# SparkFun_Qwiic_Adapter.net
KiCad netlist of a schematic drawn in EAGLE
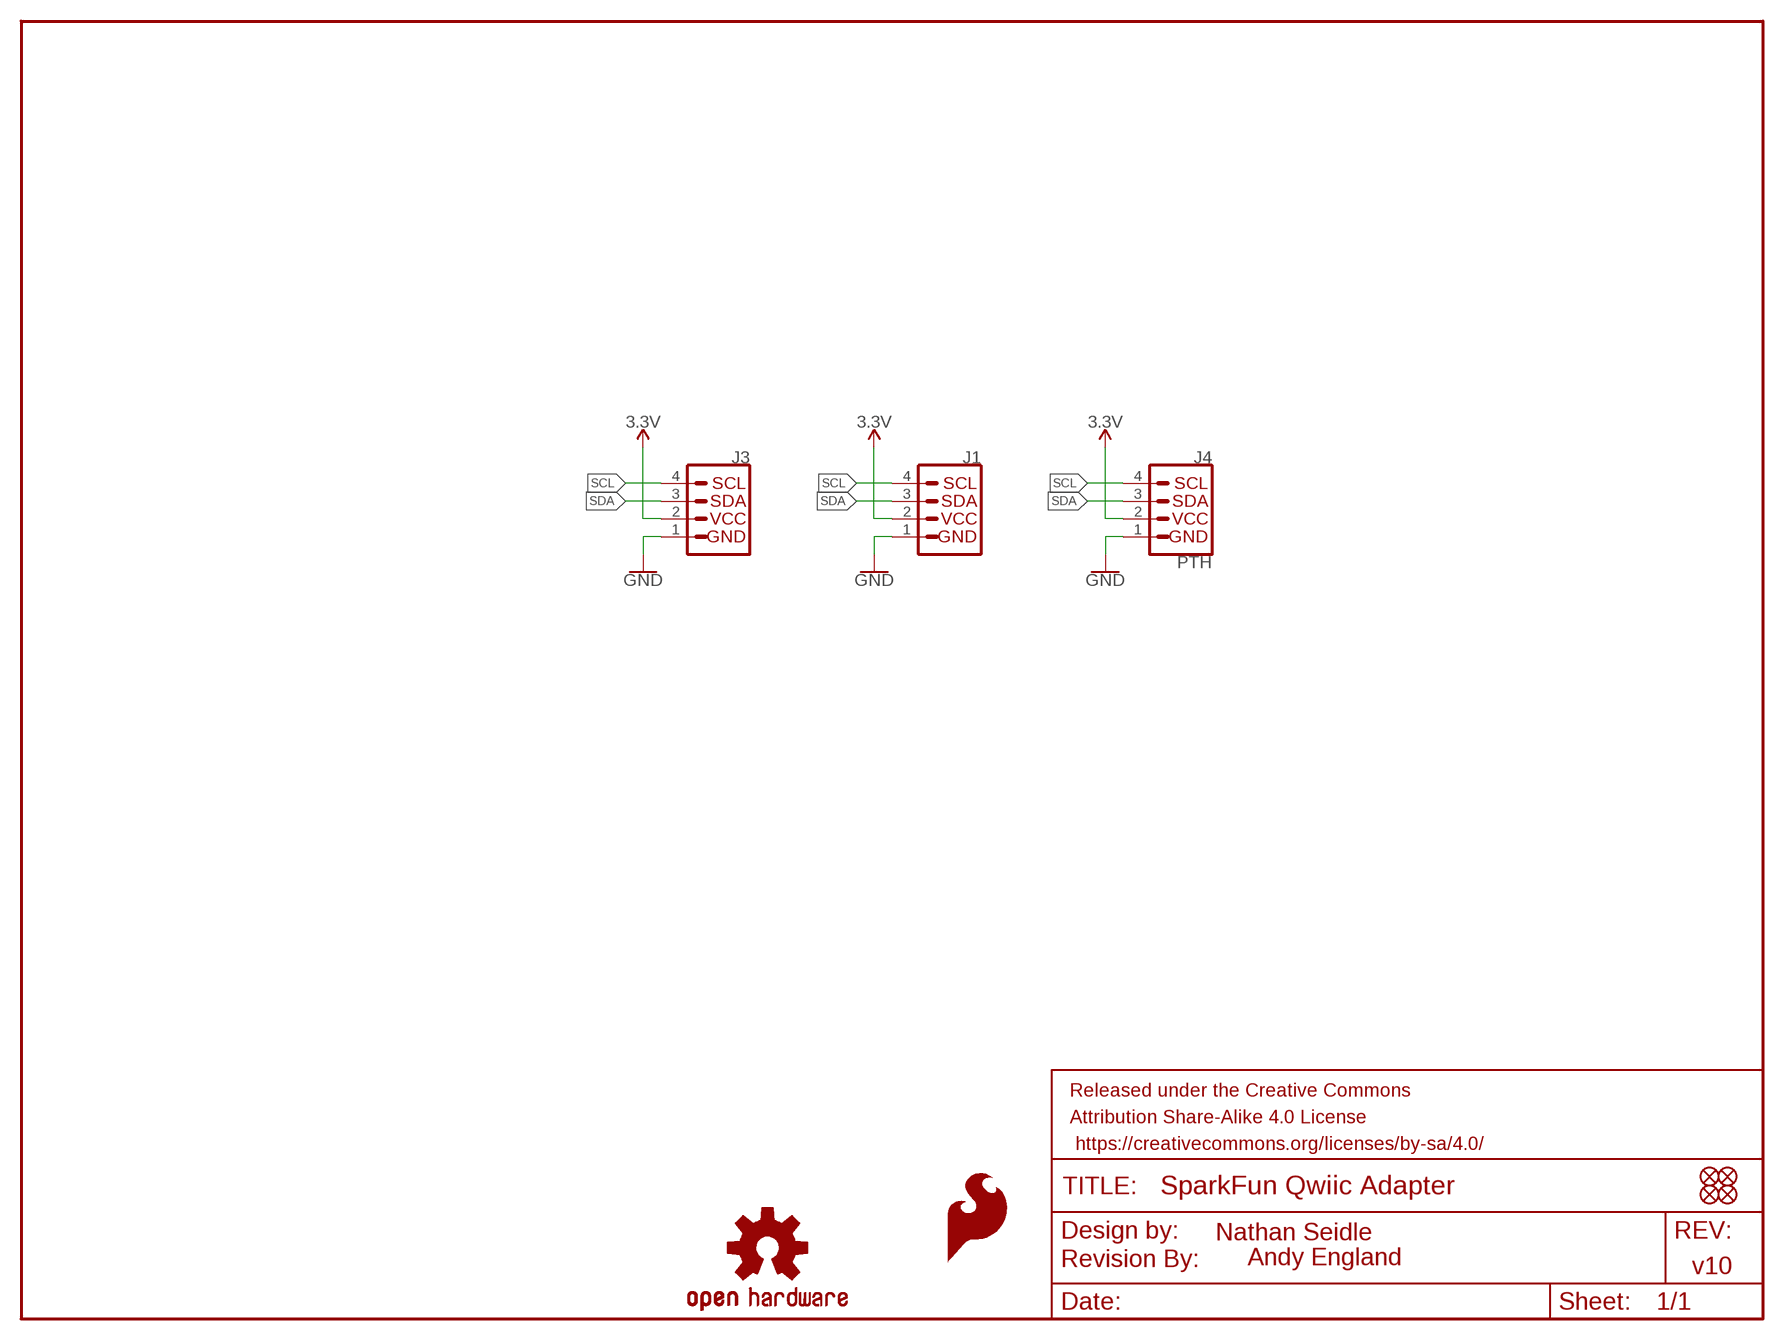
[diagram p0: schematic, sheet 1]

(export (version "E")
  (design (tool "Eeschema 10.0.6"))
  (components
    (comp (ref "FD1")
      (value "FIDUCIALUFIDUCIAL")
      (footprint "eagle-import:FIDUCIAL-MICRO")
      (libsource (lib "eagle-import") (part "FIDUCIALUFIDUCIAL"))
    )
    (comp (ref "FD2")
      (value "FIDUCIALUFIDUCIAL")
      (footprint "eagle-import:FIDUCIAL-MICRO")
      (libsource (lib "eagle-import") (part "FIDUCIALUFIDUCIAL"))
    )
    (comp (ref "FD3")
      (value "FIDUCIALUFIDUCIAL")
      (footprint "eagle-import:FIDUCIAL-MICRO")
      (libsource (lib "eagle-import") (part "FIDUCIALUFIDUCIAL"))
    )
    (comp (ref "FD4")
      (value "FIDUCIALUFIDUCIAL")
      (footprint "eagle-import:FIDUCIAL-MICRO")
      (libsource (lib "eagle-import") (part "FIDUCIALUFIDUCIAL"))
    )
    (comp (ref "FRAME1")
      (value "FRAME-LETTER")
      (footprint "eagle-import:CREATIVE_COMMONS")
      (libsource (lib "eagle-import") (part "FRAME-LETTER"))
    )
    (comp (ref "J1")
      (value "QWIIC_CONNECTORJS-1MM")
      (footprint "eagle-import:1X04_1MM_RA")
      (libsource (lib "eagle-import") (part "QWIIC_CONNECTORJS-1MM"))
    )
    (comp (ref "J3")
      (value "QWIIC_CONNECTORJS-1MM")
      (footprint "eagle-import:1X04_1MM_RA")
      (libsource (lib "eagle-import") (part "QWIIC_CONNECTORJS-1MM"))
    )
    (comp (ref "J4")
      (value "PTH")
      (footprint "eagle-import:1X04")
      (libsource (lib "eagle-import") (part "I2C_STANDARD"))
    )
    (comp (ref "LOGO1")
      (value "REVISION")
      (footprint "eagle-import:REVISION")
      (libsource (lib "eagle-import") (part "REVISION"))
    )
    (comp (ref "LOGO4")
      (value "OSHW-LOGOS")
      (footprint "eagle-import:OSHW-LOGO-S")
      (libsource (lib "eagle-import") (part "OSHW-LOGOS"))
    )
    (comp (ref "U$1")
      (value "SFE_LOGO_FLAME.1_INCH")
      (footprint "eagle-import:SFE_LOGO_FLAME_.1")
      (libsource (lib "eagle-import") (part "SFE_LOGO_FLAME.1_INCH"))
    )
  )
  (nets
    (net (code "1") (name "3.3V") (class "Default")
      (node (ref "J1") (pin "2") (pinfunction "2_2") (pintype "power_in"))
      (node (ref "J3") (pin "2") (pinfunction "2_2") (pintype "power_in"))
      (node (ref "J4") (pin "2") (pinfunction "2_2") (pintype "power_in"))
    )
    (net (code "2") (name "GND") (class "Default")
      (node (ref "J1") (pin "1") (pinfunction "1_1") (pintype "power_in"))
      (node (ref "J3") (pin "1") (pinfunction "1_1") (pintype "power_in"))
      (node (ref "J4") (pin "1") (pinfunction "1_1") (pintype "power_in"))
    )
    (net (code "3") (name "SCL") (class "Default")
      (node (ref "J1") (pin "4") (pinfunction "4_4") (pintype "passive"))
      (node (ref "J3") (pin "4") (pinfunction "4_4") (pintype "passive"))
      (node (ref "J4") (pin "4") (pinfunction "4_4") (pintype "passive"))
    )
    (net (code "4") (name "SDA") (class "Default")
      (node (ref "J1") (pin "3") (pinfunction "3_3") (pintype "passive"))
      (node (ref "J3") (pin "3") (pinfunction "3_3") (pintype "passive"))
      (node (ref "J4") (pin "3") (pinfunction "3_3") (pintype "passive"))
    )
  )
)
